# openSX70-dongle_v3-3.net
KiCad netlist of a schematic drawn in EAGLE
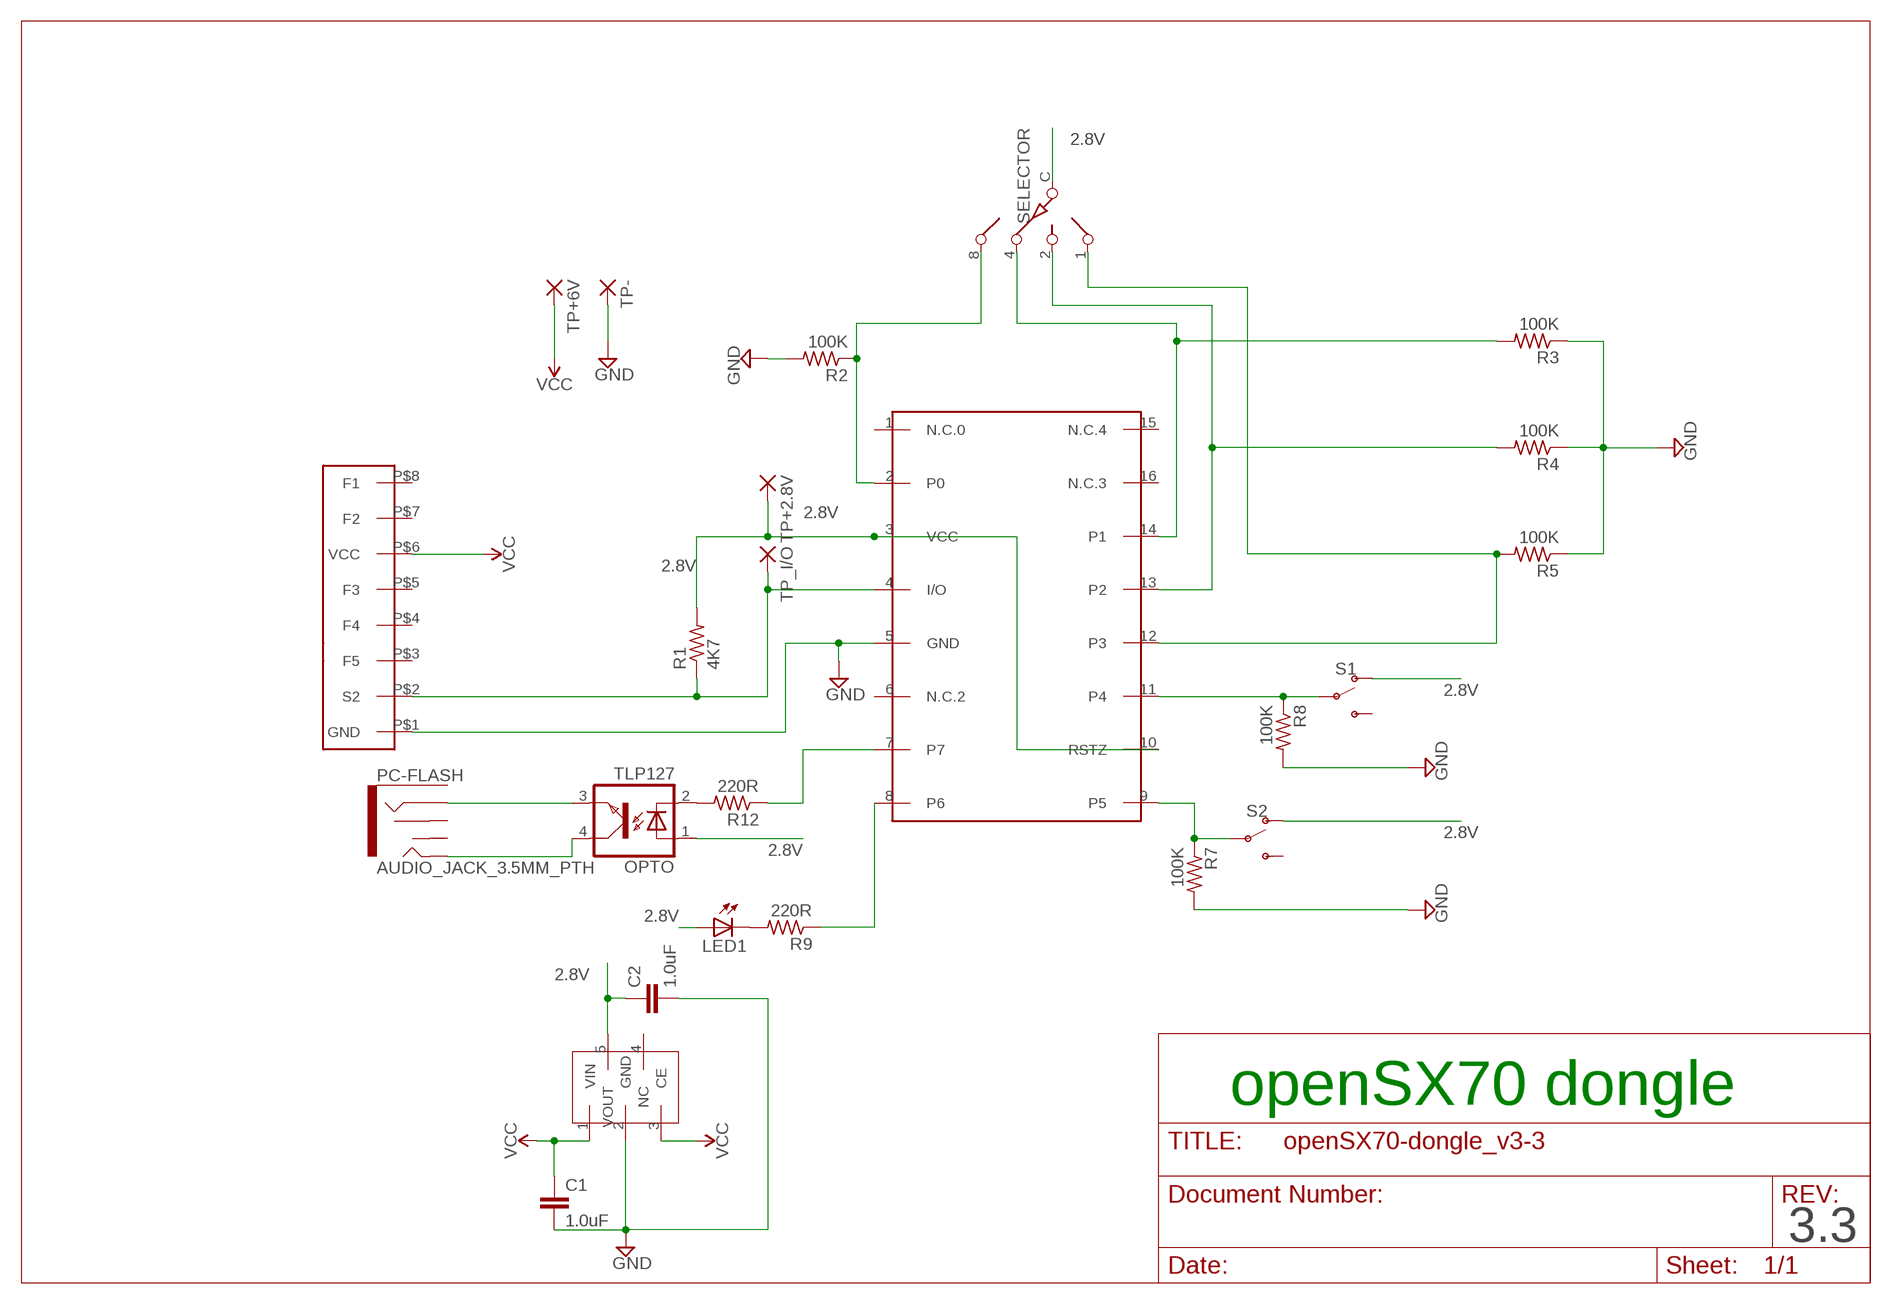
[diagram p0: schematic, sheet 1]

(export (version "E")
  (design (tool "Eeschema 10.0.6"))
  (components
    (comp (ref "C1")
      (value "1.0uF")
      (footprint "eagle-import:C0603")
      (libsource (lib "eagle-import") (part "C-EUC0603"))
    )
    (comp (ref "C2")
      (value "1.0uF")
      (footprint "eagle-import:C0603")
      (libsource (lib "eagle-import") (part "C-EUC0603"))
    )
    (comp (ref "DS2408")
      (value "DS2408")
      (footprint "eagle-import:SO16")
      (libsource (lib "eagle-import") (part "DS2408"))
    )
    (comp (ref "LED1")
      (value "LED3MM")
      (footprint "eagle-import:LED3MM")
      (libsource (lib "eagle-import") (part "LED3MM"))
    )
    (comp (ref "OPTO")
      (value "TLP127")
      (footprint "eagle-import:SO-4")
      (libsource (lib "eagle-import") (part "TLP127"))
    )
    (comp (ref "PC-FLASH")
      (value "AUDIO_JACK_3.5MM_PTH")
      (footprint "eagle-import:AUDIO-JACK")
      (libsource (lib "eagle-import") (part "AUDIO_JACK_3.5MM_PTH"))
    )
    (comp (ref "R1")
      (value "4K7")
      (footprint "eagle-import:M0805")
      (libsource (lib "eagle-import") (part "R-US_M0805"))
    )
    (comp (ref "R2")
      (value "100K")
      (footprint "eagle-import:M0805")
      (libsource (lib "eagle-import") (part "R-US_M0805"))
    )
    (comp (ref "R3")
      (value "100K")
      (footprint "eagle-import:M0805")
      (libsource (lib "eagle-import") (part "R-US_M0805"))
    )
    (comp (ref "R4")
      (value "100K")
      (footprint "eagle-import:M0805")
      (libsource (lib "eagle-import") (part "R-US_M0805"))
    )
    (comp (ref "R5")
      (value "100K")
      (footprint "eagle-import:M0805")
      (libsource (lib "eagle-import") (part "R-US_M0805"))
    )
    (comp (ref "R7")
      (value "100K")
      (footprint "eagle-import:M0805")
      (libsource (lib "eagle-import") (part "R-US_M0805"))
    )
    (comp (ref "R8")
      (value "100K")
      (footprint "eagle-import:M0805")
      (libsource (lib "eagle-import") (part "R-US_M0805"))
    )
    (comp (ref "R9")
      (value "220R")
      (footprint "eagle-import:M0805")
      (libsource (lib "eagle-import") (part "R-US_M0805"))
    )
    (comp (ref "R12")
      (value "220R")
      (footprint "eagle-import:M0805")
      (libsource (lib "eagle-import") (part "R-US_M0805"))
    )
    (comp (ref "REG")
      (value "NCP4688")
      (footprint "eagle-import:SOT-23-5")
      (libsource (lib "eagle-import") (part "NCP4688"))
    )
    (comp (ref "S1")
      (value "SWITCH-SPDT-SMD-RIGHT-ANGLE")
      (footprint "eagle-import:SWITCH_SPST_SMD_A")
      (libsource (lib "eagle-import") (part "SWITCH-SPDT-SMD-RIGHT-ANGLE"))
    )
    (comp (ref "S2")
      (value "SWITCH-SPDT-SMD-RIGHT-ANGLE")
      (footprint "eagle-import:SWITCH_SPST_SMD_A")
      (libsource (lib "eagle-import") (part "SWITCH-SPDT-SMD-RIGHT-ANGLE"))
    )
    (comp (ref "SELECTOR")
      (value "SW-C16")
      (footprint "eagle-import:SW-C16")
      (libsource (lib "eagle-import") (part "SW-C16"))
    )
    (comp (ref "TP+2.8V")
      (value "SMD2")
      (footprint "eagle-import:SMD1,27-2,54")
      (libsource (lib "eagle-import") (part "SMD2"))
    )
    (comp (ref "TP+6V")
      (value "SMD2")
      (footprint "eagle-import:SMD1,27-2,54")
      (libsource (lib "eagle-import") (part "SMD2"))
    )
    (comp (ref "TP-")
      (value "SMD2")
      (footprint "eagle-import:SMD1,27-2,54")
      (libsource (lib "eagle-import") (part "SMD2"))
    )
    (comp (ref "TP_I/O")
      (value "SMD2")
      (footprint "eagle-import:SMD1,27-2,54")
      (libsource (lib "eagle-import") (part "SMD2"))
    )
    (comp (ref "U$1")
      (value "FLASH-EDGE-CONNECTOR")
      (footprint "eagle-import:FLASH-EDGE-8")
      (libsource (lib "eagle-import") (part "FLASH-EDGE-CONNECTOR"))
    )
  )
  (nets
    (net (code "1") (name "/2.8V") (class "Default")
      (node (ref "C2") (pin "1") (pinfunction "1_1") (pintype "passive"))
      (node (ref "DS2408") (pin "10") (pinfunction "RSTZ_10") (pintype "bidirectional"))
      (node (ref "DS2408") (pin "3") (pinfunction "VCC_3") (pintype "bidirectional"))
      (node (ref "LED1") (pin "A") (pinfunction "A_A") (pintype "passive"))
      (node (ref "OPTO") (pin "1") (pinfunction "A_1") (pintype "passive"))
      (node (ref "R1") (pin "2") (pinfunction "2_2") (pintype "passive"))
      (node (ref "REG") (pin "5") (pinfunction "VOUT_5") (pintype "bidirectional"))
      (node (ref "S1") (pin "1") (pinfunction "O_1") (pintype "passive"))
      (node (ref "S2") (pin "1") (pinfunction "O_1") (pintype "passive"))
      (node (ref "SELECTOR") (pin "C") (pinfunction "C_C") (pintype "passive"))
      (node (ref "TP+2.8V") (pin "1") (pinfunction "P_1") (pintype "passive"))
    )
    (net (code "2") (name "GND") (class "Default")
      (node (ref "C1") (pin "2") (pinfunction "2_2") (pintype "passive"))
      (node (ref "C2") (pin "2") (pinfunction "2_2") (pintype "passive"))
      (node (ref "DS2408") (pin "5") (pinfunction "GND_5") (pintype "bidirectional"))
      (node (ref "R2") (pin "2") (pinfunction "2_2") (pintype "passive"))
      (node (ref "R3") (pin "1") (pinfunction "1_1") (pintype "passive"))
      (node (ref "R4") (pin "1") (pinfunction "1_1") (pintype "passive"))
      (node (ref "R5") (pin "1") (pinfunction "1_1") (pintype "passive"))
      (node (ref "R7") (pin "2") (pinfunction "2_2") (pintype "passive"))
      (node (ref "R8") (pin "2") (pinfunction "2_2") (pintype "passive"))
      (node (ref "REG") (pin "2") (pinfunction "GND_2") (pintype "bidirectional"))
      (node (ref "TP-") (pin "1") (pinfunction "P_1") (pintype "passive"))
      (node (ref "U$1") (pin "P$1") (pinfunction "GND_P$1") (pintype "bidirectional"))
    )
    (net (code "3") (name "Net-(DS2408-I{slash}O)") (class "Default")
      (node (ref "DS2408") (pin "4") (pinfunction "I/O_4") (pintype "bidirectional"))
      (node (ref "R1") (pin "1") (pinfunction "1_1") (pintype "passive"))
      (node (ref "TP_I/O") (pin "1") (pinfunction "P_1") (pintype "passive"))
      (node (ref "U$1") (pin "P$2") (pinfunction "S2_P$2") (pintype "bidirectional"))
    )
    (net (code "4") (name "Net-(DS2408-P0)") (class "Default")
      (node (ref "DS2408") (pin "2") (pinfunction "P0_2") (pintype "bidirectional"))
      (node (ref "R2") (pin "1") (pinfunction "1_1") (pintype "passive"))
      (node (ref "SELECTOR") (pin "8") (pinfunction "8_8") (pintype "passive"))
    )
    (net (code "5") (name "Net-(DS2408-P1)") (class "Default")
      (node (ref "DS2408") (pin "14") (pinfunction "P1_14") (pintype "bidirectional"))
      (node (ref "R3") (pin "2") (pinfunction "2_2") (pintype "passive"))
      (node (ref "SELECTOR") (pin "4") (pinfunction "4_4") (pintype "passive"))
    )
    (net (code "6") (name "Net-(DS2408-P2)") (class "Default")
      (node (ref "DS2408") (pin "13") (pinfunction "P2_13") (pintype "bidirectional"))
      (node (ref "R4") (pin "2") (pinfunction "2_2") (pintype "passive"))
      (node (ref "SELECTOR") (pin "2") (pinfunction "2_2") (pintype "passive"))
    )
    (net (code "7") (name "Net-(DS2408-P3)") (class "Default")
      (node (ref "DS2408") (pin "12") (pinfunction "P3_12") (pintype "bidirectional"))
      (node (ref "R5") (pin "2") (pinfunction "2_2") (pintype "passive"))
      (node (ref "SELECTOR") (pin "1") (pinfunction "1_1") (pintype "passive"))
    )
    (net (code "8") (name "Net-(DS2408-P4)") (class "Default")
      (node (ref "DS2408") (pin "11") (pinfunction "P4_11") (pintype "bidirectional"))
      (node (ref "R8") (pin "1") (pinfunction "1_1") (pintype "passive"))
      (node (ref "S1") (pin "2") (pinfunction "P_2") (pintype "passive"))
    )
    (net (code "9") (name "Net-(DS2408-P5)") (class "Default")
      (node (ref "DS2408") (pin "9") (pinfunction "P5_9") (pintype "bidirectional"))
      (node (ref "R7") (pin "1") (pinfunction "1_1") (pintype "passive"))
      (node (ref "S2") (pin "2") (pinfunction "P_2") (pintype "passive"))
    )
    (net (code "10") (name "Net-(DS2408-P6)") (class "Default")
      (node (ref "DS2408") (pin "8") (pinfunction "P6_8") (pintype "bidirectional"))
      (node (ref "R9") (pin "1") (pinfunction "1_1") (pintype "passive"))
    )
    (net (code "11") (name "Net-(DS2408-P7)") (class "Default")
      (node (ref "DS2408") (pin "7") (pinfunction "P7_7") (pintype "bidirectional"))
      (node (ref "R12") (pin "1") (pinfunction "1_1") (pintype "passive"))
    )
    (net (code "12") (name "Net-(LED1-C)") (class "Default")
      (node (ref "LED1") (pin "K") (pinfunction "C_K") (pintype "passive"))
      (node (ref "R9") (pin "2") (pinfunction "2_2") (pintype "passive"))
    )
    (net (code "13") (name "Net-(OPTO-C)") (class "Default")
      (node (ref "OPTO") (pin "2") (pinfunction "C_2") (pintype "passive"))
      (node (ref "R12") (pin "2") (pinfunction "2_2") (pintype "passive"))
    )
    (net (code "14") (name "Net-(OPTO-COL)") (class "Default")
      (node (ref "OPTO") (pin "4") (pinfunction "COL_4") (pintype "passive"))
      (node (ref "PC-FLASH") (pin "TIP") (pinfunction "TIP_TIP") (pintype "bidirectional"))
    )
    (net (code "15") (name "Net-(OPTO-EMIT)") (class "Default")
      (node (ref "OPTO") (pin "3") (pinfunction "EMIT_3") (pintype "passive"))
      (node (ref "PC-FLASH") (pin "RING") (pinfunction "RING_RING") (pintype "bidirectional"))
    )
    (net (code "16") (name "VCC") (class "Default")
      (node (ref "C1") (pin "1") (pinfunction "1_1") (pintype "passive"))
      (node (ref "REG") (pin "1") (pinfunction "VIN_1") (pintype "bidirectional"))
      (node (ref "REG") (pin "3") (pinfunction "CE_3") (pintype "bidirectional"))
      (node (ref "TP+6V") (pin "1") (pinfunction "P_1") (pintype "passive"))
      (node (ref "U$1") (pin "P$6") (pinfunction "VCC_P$6") (pintype "bidirectional"))
    )
    (net (code "17") (name "unconnected-(DS2408-N.C.0-Pad1)") (class "Default")
      (node (ref "DS2408") (pin "1") (pinfunction "N.C.0_1") (pintype "bidirectional"))
    )
    (net (code "18") (name "unconnected-(DS2408-N.C.2-Pad6)") (class "Default")
      (node (ref "DS2408") (pin "6") (pinfunction "N.C.2_6") (pintype "bidirectional"))
    )
    (net (code "19") (name "unconnected-(DS2408-N.C.3-Pad16)") (class "Default")
      (node (ref "DS2408") (pin "16") (pinfunction "N.C.3_16") (pintype "bidirectional"))
    )
    (net (code "20") (name "unconnected-(DS2408-N.C.4-Pad15)") (class "Default")
      (node (ref "DS2408") (pin "15") (pinfunction "N.C.4_15") (pintype "bidirectional"))
    )
    (net (code "21") (name "unconnected-(PC-FLASH-PadRSH)") (class "Default")
      (node (ref "PC-FLASH") (pin "RSH") (pinfunction "RSH_RSH") (pintype "bidirectional"))
    )
    (net (code "22") (name "unconnected-(PC-FLASH-PadSLEEVE)") (class "Default")
      (node (ref "PC-FLASH") (pin "SLEEVE") (pinfunction "SLEEVE_SLEEVE") (pintype "bidirectional"))
    )
    (net (code "23") (name "unconnected-(PC-FLASH-PadTSH)") (class "Default")
      (node (ref "PC-FLASH") (pin "TSH") (pinfunction "TSH_TSH") (pintype "bidirectional"))
    )
    (net (code "24") (name "unconnected-(REG-NC-Pad4)") (class "Default")
      (node (ref "REG") (pin "4") (pinfunction "NC_4") (pintype "bidirectional"))
    )
    (net (code "25") (name "unconnected-(S1-S-Pad3)") (class "Default")
      (node (ref "S1") (pin "3") (pinfunction "S_3") (pintype "passive"))
    )
    (net (code "26") (name "unconnected-(S2-S-Pad3)") (class "Default")
      (node (ref "S2") (pin "3") (pinfunction "S_3") (pintype "passive"))
    )
    (net (code "27") (name "unconnected-(U$1-F1-PadP$8)") (class "Default")
      (node (ref "U$1") (pin "P$8") (pinfunction "F1_P$8") (pintype "bidirectional"))
    )
    (net (code "28") (name "unconnected-(U$1-F2-PadP$7)") (class "Default")
      (node (ref "U$1") (pin "P$7") (pinfunction "F2_P$7") (pintype "bidirectional"))
    )
    (net (code "29") (name "unconnected-(U$1-F3-PadP$5)") (class "Default")
      (node (ref "U$1") (pin "P$5") (pinfunction "F3_P$5") (pintype "bidirectional"))
    )
    (net (code "30") (name "unconnected-(U$1-F4-PadP$4)") (class "Default")
      (node (ref "U$1") (pin "P$4") (pinfunction "F4_P$4") (pintype "bidirectional"))
    )
    (net (code "31") (name "unconnected-(U$1-F5-PadP$3)") (class "Default")
      (node (ref "U$1") (pin "P$3") (pinfunction "F5_P$3") (pintype "bidirectional"))
    )
  )
)
